# Schematica.net
KiCad netlist of a schematic drawn in EAGLE
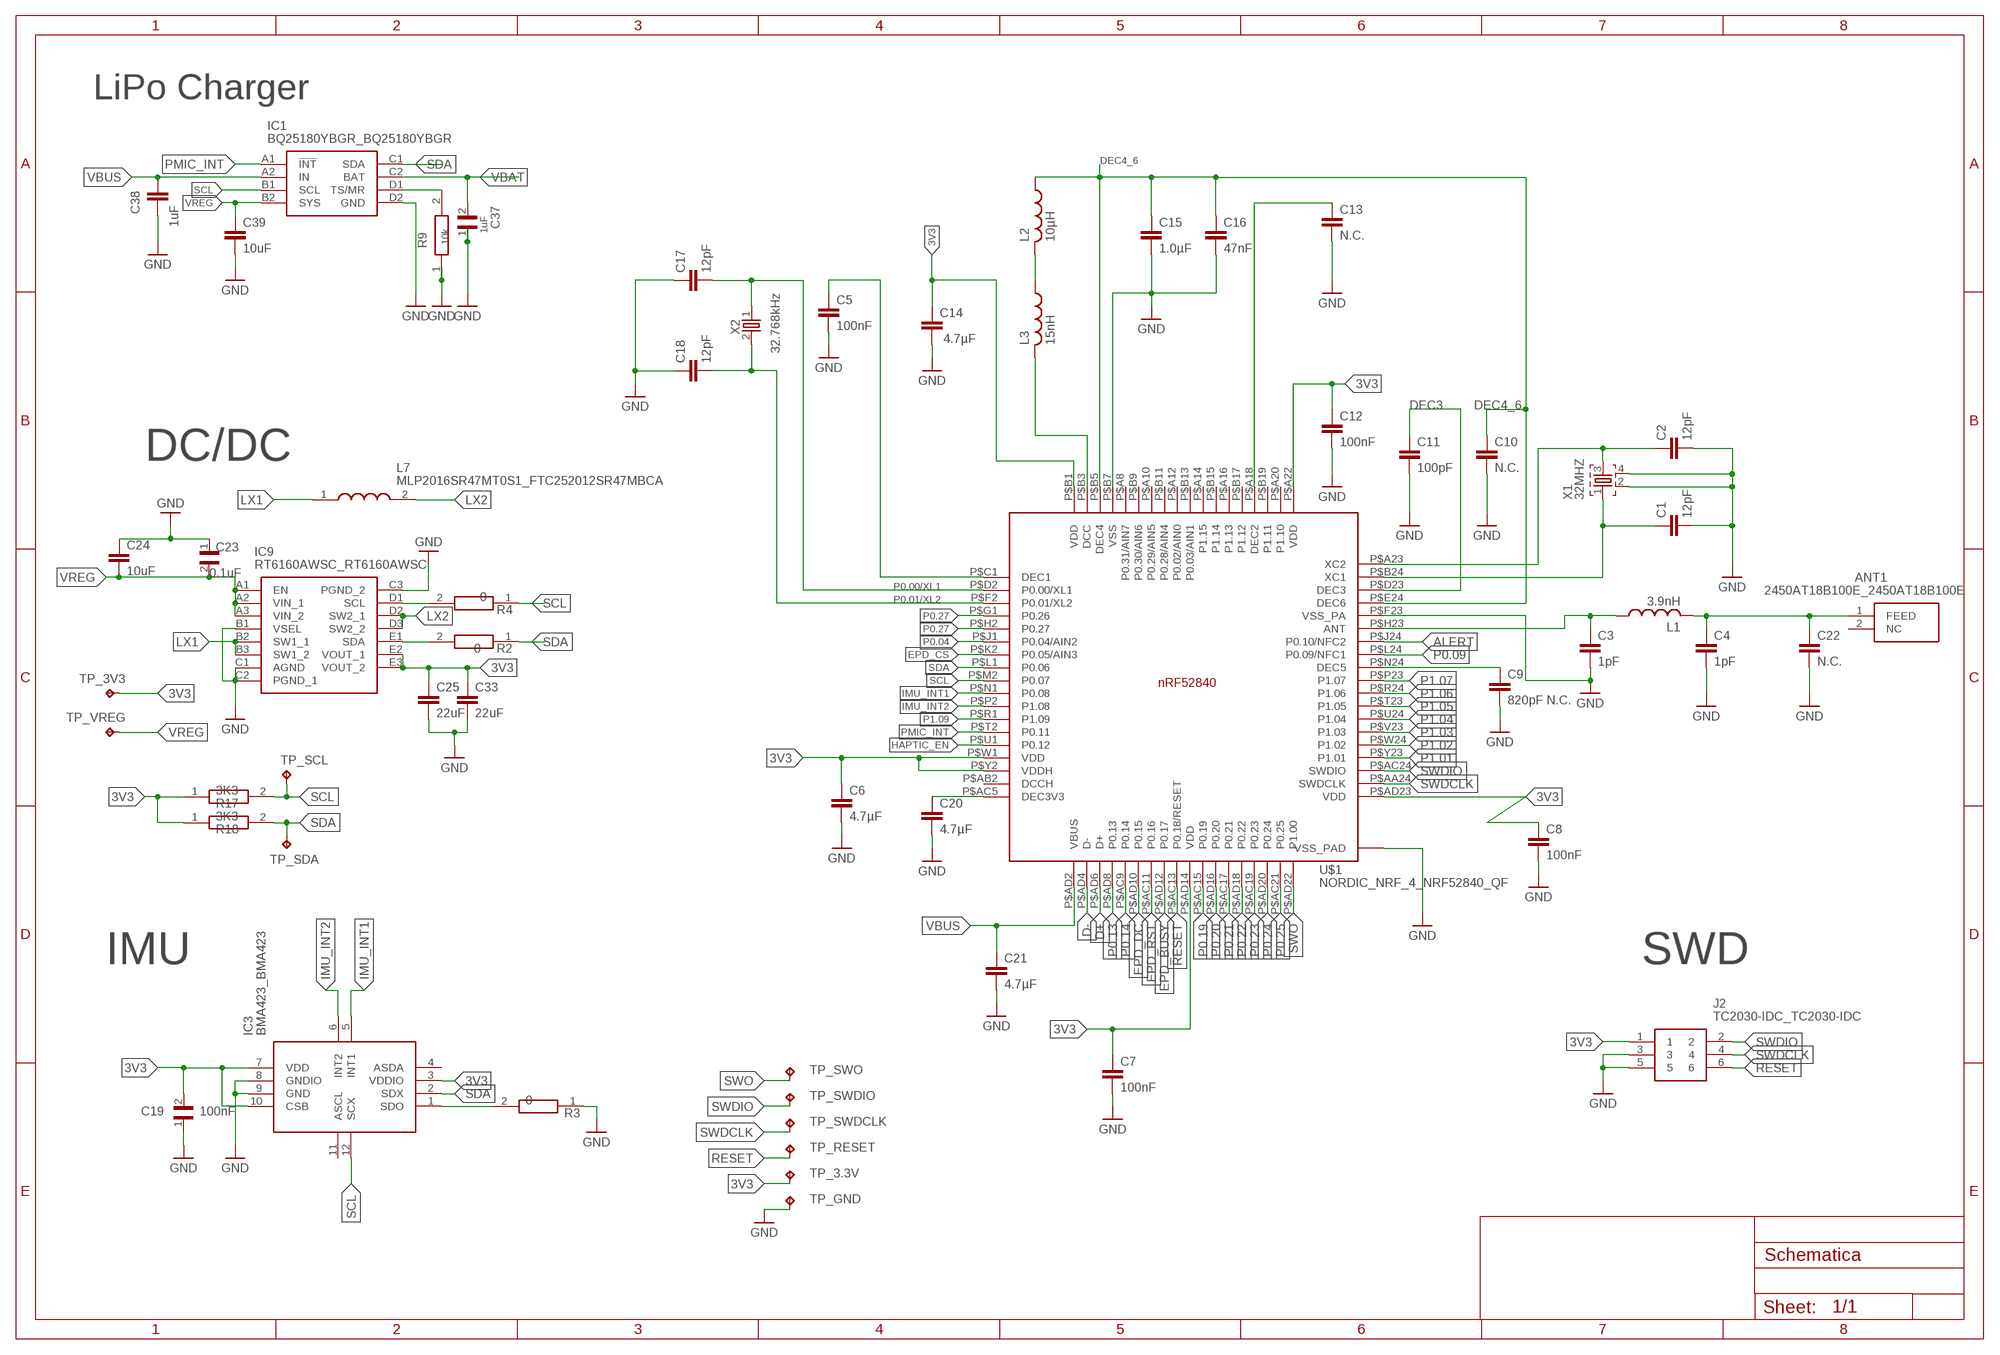
[diagram p0: schematic, sheet 1, part 1 of 2]
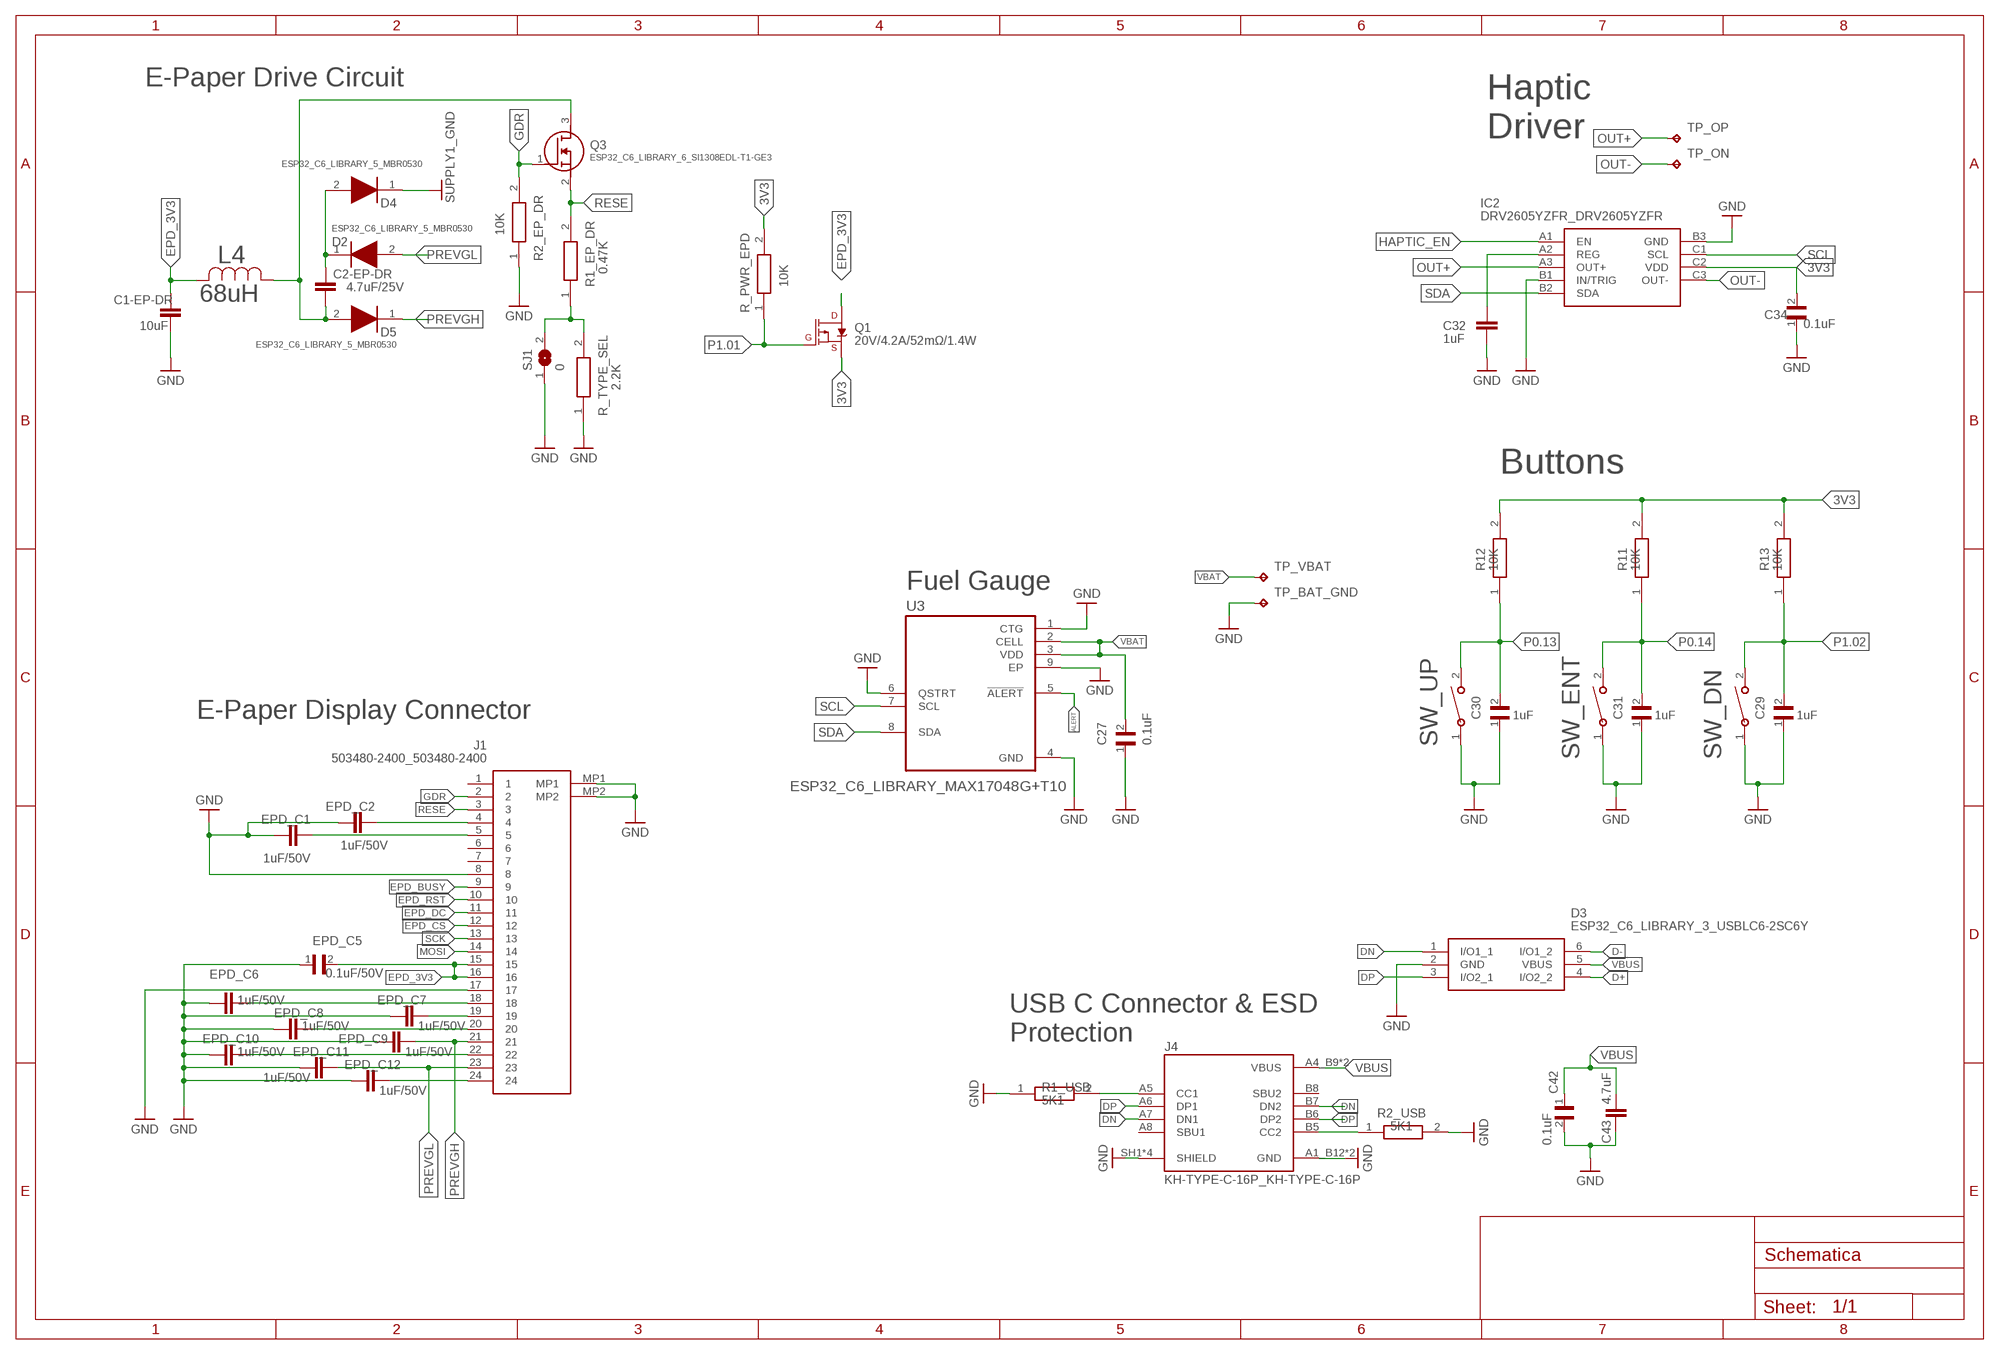
[diagram p1: schematic, sheet 1, part 2 of 2]

(export (version "E")
  (design (tool "Eeschema 10.0.6"))
  (components
    (comp (ref "ANT1")
      (value "2450AT18B100E_2450AT18B100E")
      (footprint "eagle-import:2450AT18B100E_ANTC3216X140N")
      (fields
        (field (name "ARROW_PART_NUMBER") "2450AT18B100E")
        (field (name "MOUSER_PART_NUMBER") "609-2450AT18B100E")
      )
      (libsource (lib "eagle-import") (part "2450AT18B100E_2450AT18B100E"))
    )
    (comp (ref "C1")
      (value "12pF")
      (footprint "eagle-import:NORDIC_NRF_3_RESC0402_L")
      (libsource (lib "eagle-import") (part "NORDIC_NRF_3_CAPACITOR_0402_L"))
    )
    (comp (ref "C1-EP-DR")
      (value "10uF")
      (footprint "eagle-import:PERFECT_0402_0402")
      (libsource (lib "eagle-import") (part "PERFECT_0402_CAP_0402"))
    )
    (comp (ref "C2")
      (value "12pF")
      (footprint "eagle-import:NORDIC_NRF_3_RESC0402_L")
      (libsource (lib "eagle-import") (part "NORDIC_NRF_3_CAPACITOR_0402_L"))
    )
    (comp (ref "C2-EP-DR")
      (value "4.7uF/25V")
      (footprint "eagle-import:PERFECT_0402_0402")
      (libsource (lib "eagle-import") (part "PERFECT_0402_CAP_0402"))
    )
    (comp (ref "C3")
      (value "1pF")
      (footprint "eagle-import:NORDIC_NRF_3_RESC0402_L")
      (libsource (lib "eagle-import") (part "NORDIC_NRF_3_CAPACITOR_0402_L"))
    )
    (comp (ref "C4")
      (value "1pF")
      (footprint "eagle-import:NORDIC_NRF_3_RESC0402_L")
      (libsource (lib "eagle-import") (part "NORDIC_NRF_3_CAPACITOR_0402_L"))
    )
    (comp (ref "C5")
      (value "100nF")
      (footprint "eagle-import:NORDIC_NRF_3_RESC0402_L")
      (libsource (lib "eagle-import") (part "NORDIC_NRF_3_CAPACITOR_0402_L"))
    )
    (comp (ref "C6")
      (value "4.7µF")
      (footprint "eagle-import:NORDIC_NRF_3_RESC0402_L")
      (libsource (lib "eagle-import") (part "NORDIC_NRF_3_CAPACITOR_0402_L"))
    )
    (comp (ref "C7")
      (value "100nF")
      (footprint "eagle-import:NORDIC_NRF_3_RESC0402_L")
      (libsource (lib "eagle-import") (part "NORDIC_NRF_3_CAPACITOR_0402_L"))
    )
    (comp (ref "C8")
      (value "100nF")
      (footprint "eagle-import:NORDIC_NRF_3_RESC0402_L")
      (libsource (lib "eagle-import") (part "NORDIC_NRF_3_CAPACITOR_0402_L"))
    )
    (comp (ref "C9")
      (value "820pF N.C.")
      (footprint "eagle-import:NORDIC_NRF_3_RESC0402_L")
      (libsource (lib "eagle-import") (part "NORDIC_NRF_3_CAPACITOR_0402_L"))
    )
    (comp (ref "C10")
      (value "N.C.")
      (footprint "eagle-import:NORDIC_NRF_3_RESC0402_L")
      (libsource (lib "eagle-import") (part "NORDIC_NRF_3_CAPACITOR_0402_L"))
    )
    (comp (ref "C11")
      (value "100pF")
      (footprint "eagle-import:NORDIC_NRF_3_RESC0402_L")
      (libsource (lib "eagle-import") (part "NORDIC_NRF_3_CAPACITOR_0402_L"))
    )
    (comp (ref "C12")
      (value "100nF")
      (footprint "eagle-import:NORDIC_NRF_3_RESC0402_L")
      (libsource (lib "eagle-import") (part "NORDIC_NRF_3_CAPACITOR_0402_L"))
    )
    (comp (ref "C13")
      (value "N.C.")
      (footprint "eagle-import:NORDIC_NRF_3_RESC0402_L")
      (libsource (lib "eagle-import") (part "NORDIC_NRF_3_CAPACITOR_0402_L"))
    )
    (comp (ref "C14")
      (value "4.7µF")
      (footprint "eagle-import:NORDIC_NRF_3_RESC0402_L")
      (libsource (lib "eagle-import") (part "NORDIC_NRF_3_CAPACITOR_0402_L"))
    )
    (comp (ref "C15")
      (value "1.0µF")
      (footprint "eagle-import:NORDIC_NRF_3_RESC0402_L")
      (libsource (lib "eagle-import") (part "NORDIC_NRF_3_CAPACITOR_0402_L"))
    )
    (comp (ref "C16")
      (value "47nF")
      (footprint "eagle-import:NORDIC_NRF_3_RESC0402_L")
      (libsource (lib "eagle-import") (part "NORDIC_NRF_3_CAPACITOR_0402_L"))
    )
    (comp (ref "C17")
      (value "12pF")
      (footprint "eagle-import:NORDIC_NRF_3_RESC0402_L")
      (libsource (lib "eagle-import") (part "NORDIC_NRF_3_CAPACITOR_0402_L"))
    )
    (comp (ref "C18")
      (value "12pF")
      (footprint "eagle-import:NORDIC_NRF_3_RESC0402_L")
      (libsource (lib "eagle-import") (part "NORDIC_NRF_3_CAPACITOR_0402_L"))
    )
    (comp (ref "C19")
      (value "100nF")
      (footprint "eagle-import:GRM011R60J152KE01L_1_0201")
      (libsource (lib "eagle-import") (part "GRM011R60J152KE01L_1_GRM011R60J152KE01L"))
    )
    (comp (ref "C20")
      (value "4.7µF")
      (footprint "eagle-import:NORDIC_NRF_3_RESC0402_L")
      (libsource (lib "eagle-import") (part "NORDIC_NRF_3_CAPACITOR_0402_L"))
    )
    (comp (ref "C21")
      (value "4.7µF")
      (footprint "eagle-import:NORDIC_NRF_3_RESC0402_L")
      (libsource (lib "eagle-import") (part "NORDIC_NRF_3_CAPACITOR_0402_L"))
    )
    (comp (ref "C22")
      (value "N.C.")
      (footprint "eagle-import:NORDIC_NRF_3_RESC0402_L")
      (libsource (lib "eagle-import") (part "NORDIC_NRF_3_CAPACITOR_0402_L"))
    )
    (comp (ref "C23")
      (value "0.1uF")
      (footprint "eagle-import:GRM011R60J152KE01L_1_0201")
      (libsource (lib "eagle-import") (part "GRM011R60J152KE01L_1_GRM011R60J152KE01L"))
    )
    (comp (ref "C24")
      (value "10uF")
      (footprint "eagle-import:PERFECT_0402_0402")
      (libsource (lib "eagle-import") (part "PERFECT_0402_CAP_0402"))
    )
    (comp (ref "C25")
      (value "22uF")
      (footprint "eagle-import:PERFECT_0402_0402")
      (libsource (lib "eagle-import") (part "PERFECT_0402_CAP_0402"))
    )
    (comp (ref "C27")
      (value "0.1uF")
      (footprint "eagle-import:GRM011R60J152KE01L_1_0201")
      (libsource (lib "eagle-import") (part "GRM011R60J152KE01L_1_GRM011R60J152KE01L"))
    )
    (comp (ref "C29")
      (value "GRM011R60J152KE01L_2_GRM011R60J152KE01L")
      (footprint "eagle-import:GRM011R60J152KE01L_2_CAPC0201X13N")
      (fields (field (name "MF") "Murata") (field (name "MP") "GRM011R60J152KE01L"))
      (libsource (lib "eagle-import") (part "GRM011R60J152KE01L_2_GRM011R60J152KE01L"))
    )
    (comp (ref "C30")
      (value "GRM011R60J152KE01L_2_GRM011R60J152KE01L")
      (footprint "eagle-import:GRM011R60J152KE01L_2_CAPC0201X13N")
      (fields (field (name "MF") "Murata") (field (name "MP") "GRM011R60J152KE01L"))
      (libsource (lib "eagle-import") (part "GRM011R60J152KE01L_2_GRM011R60J152KE01L"))
    )
    (comp (ref "C31")
      (value "GRM011R60J152KE01L_2_GRM011R60J152KE01L")
      (footprint "eagle-import:GRM011R60J152KE01L_2_CAPC0201X13N")
      (fields (field (name "MF") "Murata") (field (name "MP") "GRM011R60J152KE01L"))
      (libsource (lib "eagle-import") (part "GRM011R60J152KE01L_2_GRM011R60J152KE01L"))
    )
    (comp (ref "C32")
      (value "1uF")
      (footprint "eagle-import:PERFECT_0402_0402")
      (libsource (lib "eagle-import") (part "PERFECT_0402_CAP_0402"))
    )
    (comp (ref "C33")
      (value "22uF")
      (footprint "eagle-import:PERFECT_0402_0402")
      (libsource (lib "eagle-import") (part "PERFECT_0402_CAP_0402"))
    )
    (comp (ref "C34")
      (value "0.1uF")
      (footprint "eagle-import:GRM011R60J152KE01L_1_0201")
      (libsource (lib "eagle-import") (part "GRM011R60J152KE01L_1_GRM011R60J152KE01L"))
    )
    (comp (ref "C37")
      (value "GRM011R60J152KE01L_2_GRM011R60J152KE01L")
      (footprint "eagle-import:GRM011R60J152KE01L_2_CAPC0201X13N")
      (fields (field (name "MF") "Murata") (field (name "MP") "GRM011R60J152KE01L"))
      (libsource (lib "eagle-import") (part "GRM011R60J152KE01L_2_GRM011R60J152KE01L"))
    )
    (comp (ref "C38")
      (value "1uF")
      (footprint "eagle-import:PERFECT_0402_0402")
      (libsource (lib "eagle-import") (part "PERFECT_0402_CAP_0402"))
    )
    (comp (ref "C39")
      (value "10uF")
      (footprint "eagle-import:PERFECT_0402_0402")
      (libsource (lib "eagle-import") (part "PERFECT_0402_CAP_0402"))
    )
    (comp (ref "C42")
      (value "0.1uF")
      (footprint "eagle-import:GRM011R60J152KE01L_1_0201")
      (libsource (lib "eagle-import") (part "GRM011R60J152KE01L_1_GRM011R60J152KE01L"))
    )
    (comp (ref "C43")
      (value "4.7uF")
      (footprint "eagle-import:PERFECT_0402_0402")
      (libsource (lib "eagle-import") (part "PERFECT_0402_CAP_0402"))
    )
    (comp (ref "D2")
      (value "ESP32_C6_LIBRARY_5_MBR0530")
      (footprint "eagle-import:ESP32_C6_LIBRARY_5_SOD3716X135N")
      (fields (field (name "MF") "ON Semiconductor") (field (name "MP") "MBR0530"))
      (libsource (lib "eagle-import") (part "ESP32_C6_LIBRARY_5_MBR0530"))
    )
    (comp (ref "D3")
      (value "ESP32_C6_LIBRARY_3_USBLC6-2SC6Y")
      (footprint "eagle-import:ESP32_C6_LIBRARY_3_SOT95P280X145-6N")
      (fields (field (name "MF") "STMicroelectronics") (field (name "MP") "USBLC6-2SC6Y"))
      (libsource (lib "eagle-import") (part "ESP32_C6_LIBRARY_3_USBLC6-2SC6Y"))
    )
    (comp (ref "D4")
      (value "ESP32_C6_LIBRARY_5_MBR0530")
      (footprint "eagle-import:ESP32_C6_LIBRARY_5_SOD3716X135N")
      (fields (field (name "MF") "ON Semiconductor") (field (name "MP") "MBR0530"))
      (libsource (lib "eagle-import") (part "ESP32_C6_LIBRARY_5_MBR0530"))
    )
    (comp (ref "D5")
      (value "ESP32_C6_LIBRARY_5_MBR0530")
      (footprint "eagle-import:ESP32_C6_LIBRARY_5_SOD3716X135N")
      (fields (field (name "MF") "ON Semiconductor") (field (name "MP") "MBR0530"))
      (libsource (lib "eagle-import") (part "ESP32_C6_LIBRARY_5_MBR0530"))
    )
    (comp (ref "EPD_C1")
      (value "1uF/50V")
      (footprint "eagle-import:PERFECT_0402_0402")
      (libsource (lib "eagle-import") (part "PERFECT_0402_CAP_0402"))
    )
    (comp (ref "EPD_C2")
      (value "1uF/50V")
      (footprint "eagle-import:PERFECT_0402_0402")
      (libsource (lib "eagle-import") (part "PERFECT_0402_CAP_0402"))
    )
    (comp (ref "EPD_C5")
      (value "0.1uF/50V")
      (footprint "eagle-import:GRM011R60J152KE01L_1_0201")
      (libsource (lib "eagle-import") (part "GRM011R60J152KE01L_1_GRM011R60J152KE01L"))
    )
    (comp (ref "EPD_C6")
      (value "1uF/50V")
      (footprint "eagle-import:PERFECT_0402_0402")
      (libsource (lib "eagle-import") (part "PERFECT_0402_CAP_0402"))
    )
    (comp (ref "EPD_C7")
      (value "1uF/50V")
      (footprint "eagle-import:PERFECT_0402_0402")
      (libsource (lib "eagle-import") (part "PERFECT_0402_CAP_0402"))
    )
    (comp (ref "EPD_C8")
      (value "1uF/50V")
      (footprint "eagle-import:PERFECT_0402_0402")
      (libsource (lib "eagle-import") (part "PERFECT_0402_CAP_0402"))
    )
    (comp (ref "EPD_C9")
      (value "1uF/50V")
      (footprint "eagle-import:PERFECT_0402_0402")
      (libsource (lib "eagle-import") (part "PERFECT_0402_CAP_0402"))
    )
    (comp (ref "EPD_C10")
      (value "1uF/50V")
      (footprint "eagle-import:PERFECT_0402_0402")
      (libsource (lib "eagle-import") (part "PERFECT_0402_CAP_0402"))
    )
    (comp (ref "EPD_C11")
      (value "1uF/50V")
      (footprint "eagle-import:PERFECT_0402_0402")
      (libsource (lib "eagle-import") (part "PERFECT_0402_CAP_0402"))
    )
    (comp (ref "EPD_C12")
      (value "1uF/50V")
      (footprint "eagle-import:PERFECT_0402_0402")
      (libsource (lib "eagle-import") (part "PERFECT_0402_CAP_0402"))
    )
    (comp (ref "IC1")
      (value "BQ25180YBGR_BQ25180YBGR")
      (footprint "eagle-import:BQ25180YBGR_BGA8C40P2X4_100X155X50")
      (fields
        (field (name "ARROW_PART_NUMBER") "BQ25180YBGR")
        (field (name "MOUSER_PART_NUMBER") "595-BQ25180YBGR")
      )
      (libsource (lib "eagle-import") (part "BQ25180YBGR_BQ25180YBGR"))
    )
    (comp (ref "IC2")
      (value "DRV2605YZFR_DRV2605YZFR")
      (footprint "eagle-import:DRV2605YZFR_BGA9C50P3X3_144X144X62")
      (fields (field (name "ARROW_PART_NUMBER") "DRV2605YZFR"))
      (libsource (lib "eagle-import") (part "DRV2605YZFR_DRV2605YZFR"))
    )
    (comp (ref "IC3")
      (value "BMA423_BMA423")
      (footprint "eagle-import:BMA423_BMA423")
      (fields (field (name "ARROW_PART_NUMBER") "BMA423") (field (name "MOUSER_PART_NUMBER") "262-BMA423"))
      (libsource (lib "eagle-import") (part "BMA423_BMA423"))
    )
    (comp (ref "IC9")
      (value "RT6160AWSC_RT6160AWSC")
      (footprint "eagle-import:RT6160AWSC_BGA15C40P3X5_140X230X60")
      (fields
        (field (name "MANUFACTURER_PART_NUMBER") "RT6160AWSC")
        (field (name "MOUSER_PART_NUMBER") "835-RT6160AWSC")
      )
      (libsource (lib "eagle-import") (part "RT6160AWSC_RT6160AWSC"))
    )
    (comp (ref "J1")
      (value "503480-2400_503480-2400")
      (footprint "eagle-import:503480-2400_5034802400")
      (fields
        (field (name "MANUFACTURER_PART_NUMBER") "503480-2400")
        (field (name "MOUSER_PART_NUMBER") "538-503480-2400")
      )
      (libsource (lib "eagle-import") (part "503480-2400_503480-2400"))
    )
    (comp (ref "J2")
      (value "TC2030-IDC_TC2030-IDC")
      (footprint "eagle-import:TC2030-IDC_TC2030IDC")
      (fields (field (name "MANUFACTURER_PART_NUMBER") "TC2030-IDC"))
      (libsource (lib "eagle-import") (part "TC2030-IDC_TC2030-IDC"))
    )
    (comp (ref "J4")
      (value "KH-TYPE-C-16P_KH-TYPE-C-16P")
      (footprint "eagle-import:KH-TYPE-C-16P_KINGHELM_KH-TYPE-C-16P")
      (fields (field (name "MF") "kinghelm") (field (name "MP") "KH-TYPE-C-16P"))
      (libsource (lib "eagle-import") (part "KH-TYPE-C-16P_KH-TYPE-C-16P"))
    )
    (comp (ref "L1")
      (value "3.9nH")
      (footprint "eagle-import:NORDIC_NRF_2_RESC0402_L")
      (libsource (lib "eagle-import") (part "NORDIC_NRF_2_INDUCTOR_0402_L"))
    )
    (comp (ref "L2")
      (value "10µH")
      (footprint "eagle-import:NORDIC_NRF_2_RESC0402_L")
      (libsource (lib "eagle-import") (part "NORDIC_NRF_2_INDUCTOR_0402_L"))
    )
    (comp (ref "L3")
      (value "15nH")
      (footprint "eagle-import:NORDIC_NRF_2_RESC0402_L")
      (libsource (lib "eagle-import") (part "NORDIC_NRF_2_INDUCTOR_0402_L"))
    )
    (comp (ref "L4")
      (value "68uH")
      (footprint "eagle-import:ESP32_C6_LIBRARY_2_IND_4828-WE-TPC_WRE")
      (fields
        (field (name "MANUFACTURER_PART_NUMBER") "744043680")
        (field (name "COPYRIGHT") "Copyright (C) 2024 Ultra Librarian. All rights reserved.")
      )
      (libsource (lib "eagle-import") (part "ESP32_C6_LIBRARY_2_744043680IND_4828-WE-TPC_WRE"))
    )
    (comp (ref "L7")
      (value "MLP2016SR47MT0S1_FTC252012SR47MBCA")
      (footprint "eagle-import:MLP2016SR47MT0S1_INDC2016X100N")
      (fields (field (name "MANUFACTURER_PART_NUMBER") "FTC252012SR47MBCA"))
      (libsource (lib "eagle-import") (part "MLP2016SR47MT0S1_FTC252012SR47MBCA"))
    )
    (comp (ref "Q1")
      (value "20V/4.2A/52mΩ/1.4W")
      (footprint "eagle-import:ESP32_C6_LIBRARY_4_ESP32_C6_LIBRARY_4_ESP32_C6_LIBRARY_4_ESP32_C6_LIBRARY_4_ESP32_WROVER_SPARKFUN-DISCRETESEMI_SOT23-3")
      (libsource (lib "eagle-import") (part "ESP32_C6_LIBRARY_4_ESP32_WROVER_SPARKFUN-DISCRETESEMI_MOSFET_PCH-DMG2305UX-7"))
    )
    (comp (ref "Q3")
      (value "ESP32_C6_LIBRARY_6_SI1308EDL-T1-GE3")
      (footprint "eagle-import:ESP32_C6_LIBRARY_6_SOT65P210X110-3N")
      (fields (field (name "MF") "Vishay Siliconix") (field (name "MP") "SI1308EDL-T1-GE3"))
      (libsource (lib "eagle-import") (part "ESP32_C6_LIBRARY_6_SI1308EDL-T1-GE3"))
    )
    (comp (ref "R1_EP_DR")
      (value "0.47K")
      (footprint "eagle-import:CPF0201D7K68C1_0201")
      (libsource (lib "eagle-import") (part "CPF0201D7K68C1_CPF0201D7K68C1"))
    )
    (comp (ref "R1_USB")
      (value "5K1")
      (footprint "eagle-import:CPF0201D7K68C1_0201")
      (libsource (lib "eagle-import") (part "CPF0201D7K68C1_CPF0201D7K68C1"))
    )
    (comp (ref "R2")
      (value "0")
      (footprint "eagle-import:CPF0201D7K68C1_0201")
      (libsource (lib "eagle-import") (part "CPF0201D7K68C1_CPF0201D7K68C1"))
    )
    (comp (ref "R2_EP_DR")
      (value "10K")
      (footprint "eagle-import:CPF0201D7K68C1_0201")
      (libsource (lib "eagle-import") (part "CPF0201D7K68C1_CPF0201D7K68C1"))
    )
    (comp (ref "R2_USB")
      (value "5K1")
      (footprint "eagle-import:CPF0201D7K68C1_0201")
      (libsource (lib "eagle-import") (part "CPF0201D7K68C1_CPF0201D7K68C1"))
    )
    (comp (ref "R3")
      (value "0")
      (footprint "eagle-import:CPF0201D7K68C1_0201")
      (libsource (lib "eagle-import") (part "CPF0201D7K68C1_CPF0201D7K68C1"))
    )
    (comp (ref "R4")
      (value "0")
      (footprint "eagle-import:CPF0201D7K68C1_0201")
      (libsource (lib "eagle-import") (part "CPF0201D7K68C1_CPF0201D7K68C1"))
    )
    (comp (ref "R9")
      (value "ERA-1AEB3401C_CPF0201D7K68C1")
      (footprint "eagle-import:ERA-1AEB3401C_0201")
      (libsource (lib "eagle-import") (part "ERA-1AEB3401C_CPF0201D7K68C1"))
    )
    (comp (ref "R11")
      (value "10K")
      (footprint "eagle-import:CPF0201D7K68C1_0201")
      (libsource (lib "eagle-import") (part "CPF0201D7K68C1_CPF0201D7K68C1"))
    )
    (comp (ref "R12")
      (value "10K")
      (footprint "eagle-import:CPF0201D7K68C1_0201")
      (libsource (lib "eagle-import") (part "CPF0201D7K68C1_CPF0201D7K68C1"))
    )
    (comp (ref "R13")
      (value "10K")
      (footprint "eagle-import:CPF0201D7K68C1_0201")
      (libsource (lib "eagle-import") (part "CPF0201D7K68C1_CPF0201D7K68C1"))
    )
    (comp (ref "R17")
      (value "3K3")
      (footprint "eagle-import:CPF0201D7K68C1_0201")
      (libsource (lib "eagle-import") (part "CPF0201D7K68C1_CPF0201D7K68C1"))
    )
    (comp (ref "R18")
      (value "3K3")
      (footprint "eagle-import:CPF0201D7K68C1_0201")
      (libsource (lib "eagle-import") (part "CPF0201D7K68C1_CPF0201D7K68C1"))
    )
    (comp (ref "R_PWR_EPD")
      (value "10K")
      (footprint "eagle-import:CPF0201D7K68C1_0201")
      (libsource (lib "eagle-import") (part "CPF0201D7K68C1_CPF0201D7K68C1"))
    )
    (comp (ref "R_TYPE_SEL")
      (value "2.2K")
      (footprint "eagle-import:CPF0201D7K68C1_0201")
      (libsource (lib "eagle-import") (part "CPF0201D7K68C1_CPF0201D7K68C1"))
    )
    (comp (ref "SJ1")
      (value "0")
      (footprint "eagle-import:ESP32_C6_LIBRARY_7_JUMPER_SJ")
      (libsource (lib "eagle-import") (part "ESP32_C6_LIBRARY_7_JUMPER_SJ"))
    )
    (comp (ref "SW_DN")
      (value "2025-10-22_07-23-44_LIBRARY_EVP-AKE31ASW_EVP-AKE31A_PAN")
      (footprint "eagle-import:2025-10-22_07-23-44_LIBRARY_SW_EVP-AKE31A_PAN")
      (fields
        (field (name "MANUFACTURER_PART_NUMBER") "EVP-AKE31A")
        (field (name "COPYRIGHT") "Copyright (C) 2025 Ultra Librarian. All rights reserved.")
      )
      (libsource (lib "eagle-import") (part "2025-10-22_07-23-44_LIBRARY_EVP-AKE31ASW_EVP-AKE31A_PAN"))
    )
    (comp (ref "SW_ENT")
      (value "2025-10-22_07-23-44_LIBRARY_EVP-AKE31ASW_EVP-AKE31A_PAN")
      (footprint "eagle-import:2025-10-22_07-23-44_LIBRARY_SW_EVP-AKE31A_PAN")
      (fields
        (field (name "MANUFACTURER_PART_NUMBER") "EVP-AKE31A")
        (field (name "COPYRIGHT") "Copyright (C) 2025 Ultra Librarian. All rights reserved.")
      )
      (libsource (lib "eagle-import") (part "2025-10-22_07-23-44_LIBRARY_EVP-AKE31ASW_EVP-AKE31A_PAN"))
    )
    (comp (ref "SW_UP")
      (value "2025-10-22_07-23-44_LIBRARY_EVP-AKE31ASW_EVP-AKE31A_PAN")
      (footprint "eagle-import:2025-10-22_07-23-44_LIBRARY_SW_EVP-AKE31A_PAN")
      (fields
        (field (name "MANUFACTURER_PART_NUMBER") "EVP-AKE31A")
        (field (name "COPYRIGHT") "Copyright (C) 2025 Ultra Librarian. All rights reserved.")
      )
      (libsource (lib "eagle-import") (part "2025-10-22_07-23-44_LIBRARY_EVP-AKE31ASW_EVP-AKE31A_PAN"))
    )
    (comp (ref "TP_3.3V")
      (value "HECTOR_WATCH_1_TPTP20R")
      (footprint "eagle-import:HECTOR_WATCH_1_TP20R")
      (libsource (lib "eagle-import") (part "HECTOR_WATCH_1_TPTP20R"))
    )
    (comp (ref "TP_3V3")
      (value "HECTOR_WATCH_1_TPTP20R")
      (footprint "eagle-import:HECTOR_WATCH_1_TP20R")
      (libsource (lib "eagle-import") (part "HECTOR_WATCH_1_TPTP20R"))
    )
    (comp (ref "TP_BAT_GND")
      (value "HECTOR_WATCH_1_TPTP20R")
      (footprint "eagle-import:HECTOR_WATCH_1_TP20R")
      (libsource (lib "eagle-import") (part "HECTOR_WATCH_1_TPTP20R"))
    )
    (comp (ref "TP_GND")
      (value "HECTOR_WATCH_1_TPTP20R")
      (footprint "eagle-import:HECTOR_WATCH_1_TP20R")
      (libsource (lib "eagle-import") (part "HECTOR_WATCH_1_TPTP20R"))
    )
    (comp (ref "TP_ON")
      (value "HECTOR_WATCH_1_TPTP20R")
      (footprint "eagle-import:HECTOR_WATCH_1_TP20R")
      (libsource (lib "eagle-import") (part "HECTOR_WATCH_1_TPTP20R"))
    )
    (comp (ref "TP_OP")
      (value "HECTOR_WATCH_1_TPTP20R")
      (footprint "eagle-import:HECTOR_WATCH_1_TP20R")
      (libsource (lib "eagle-import") (part "HECTOR_WATCH_1_TPTP20R"))
    )
    (comp (ref "TP_RESET")
      (value "HECTOR_WATCH_1_TPTP20R")
      (footprint "eagle-import:HECTOR_WATCH_1_TP20R")
      (libsource (lib "eagle-import") (part "HECTOR_WATCH_1_TPTP20R"))
    )
    (comp (ref "TP_SCL")
      (value "HECTOR_WATCH_1_TPTP20R")
      (footprint "eagle-import:HECTOR_WATCH_1_TP20R")
      (libsource (lib "eagle-import") (part "HECTOR_WATCH_1_TPTP20R"))
    )
    (comp (ref "TP_SDA")
      (value "HECTOR_WATCH_1_TPTP20R")
      (footprint "eagle-import:HECTOR_WATCH_1_TP20R")
      (libsource (lib "eagle-import") (part "HECTOR_WATCH_1_TPTP20R"))
    )
    (comp (ref "TP_SWDCLK")
      (value "HECTOR_WATCH_1_TPTP20R")
      (footprint "eagle-import:HECTOR_WATCH_1_TP20R")
      (libsource (lib "eagle-import") (part "HECTOR_WATCH_1_TPTP20R"))
    )
    (comp (ref "TP_SWDIO")
      (value "HECTOR_WATCH_1_TPTP20R")
      (footprint "eagle-import:HECTOR_WATCH_1_TP20R")
      (libsource (lib "eagle-import") (part "HECTOR_WATCH_1_TPTP20R"))
    )
    (comp (ref "TP_SWO")
      (value "HECTOR_WATCH_1_TPTP20R")
      (footprint "eagle-import:HECTOR_WATCH_1_TP20R")
      (libsource (lib "eagle-import") (part "HECTOR_WATCH_1_TPTP20R"))
    )
    (comp (ref "TP_VBAT")
      (value "HECTOR_WATCH_1_TPTP20R")
      (footprint "eagle-import:HECTOR_WATCH_1_TP20R")
      (libsource (lib "eagle-import") (part "HECTOR_WATCH_1_TPTP20R"))
    )
    (comp (ref "TP_VREG")
      (value "HECTOR_WATCH_1_TPTP20R")
      (footprint "eagle-import:HECTOR_WATCH_1_TP20R")
      (libsource (lib "eagle-import") (part "HECTOR_WATCH_1_TPTP20R"))
    )
    (comp (ref "U$1")
      (value "NORDIC_NRF_4_NRF52840_QF")
      (footprint "eagle-import:NORDIC_NRF_4_AQFN50P700X700X85_HS-74N")
      (libsource (lib "eagle-import") (part "NORDIC_NRF_4_NRF52840_QF"))
    )
    (comp (ref "U3")
      (value "ESP32_C6_LIBRARY_MAX17048G+T10")
      (footprint "eagle-import:ESP32_C6_LIBRARY_SON50P200X200X80-9N")
      (fields (field (name "MF") "Analog Devices") (field (name "MP") "MAX17048G+T10"))
      (libsource (lib "eagle-import") (part "ESP32_C6_LIBRARY_MAX17048G+T10"))
    )
    (comp (ref "X1")
      (value "32MHZ")
      (footprint "eagle-import:NORDIC_NRF_BT-XTAL_2016_N")
      (libsource (lib "eagle-import") (part "NORDIC_NRF_XTAL_32MHZ"))
    )
    (comp (ref "X2")
      (value "32.768kHz")
      (footprint "eagle-import:NORDIC_NRF_1_XTAL_3215_N")
      (libsource (lib "eagle-import") (part "NORDIC_NRF_1_XTAL_32KHZ"))
    )
  )
  (nets
    (net (code "1") (name "/DEC3") (class "Default")
      (node (ref "C11") (pin "1") (pinfunction "1_1") (pintype "passive"))
      (node (ref "U$1") (pin "P$D23") (pinfunction "DEC3_P$D23") (pintype "bidirectional"))
    )
    (net (code "2") (name "/DEC4_6") (class "Default")
      (node (ref "C10") (pin "1") (pinfunction "1_1") (pintype "passive"))
      (node (ref "C15") (pin "1") (pinfunction "1_1") (pintype "passive"))
      (node (ref "C16") (pin "1") (pinfunction "1_1") (pintype "passive"))
      (node (ref "L2") (pin "1") (pinfunction "1_1") (pintype "passive"))
      (node (ref "U$1") (pin "P$B5") (pinfunction "DEC4_P$B5") (pintype "power_in"))
      (node (ref "U$1") (pin "P$E24") (pinfunction "DEC6_P$E24") (pintype "bidirectional"))
    )
    (net (code "3") (name "/P0.00{slash}XL1") (class "Default")
      (node (ref "C17") (pin "2") (pinfunction "2_2") (pintype "passive"))
      (node (ref "U$1") (pin "P$D2") (pinfunction "P0.00/XL1_P$D2") (pintype "bidirectional"))
      (node (ref "X2") (pin "1") (pinfunction "1_1") (pintype "passive"))
    )
    (net (code "4") (name "/P0.01{slash}XL2") (class "Default")
      (node (ref "C18") (pin "2") (pinfunction "2_2") (pintype "passive"))
      (node (ref "U$1") (pin "P$F2") (pinfunction "P0.01/XL2_P$F2") (pintype "bidirectional"))
      (node (ref "X2") (pin "2") (pinfunction "2_2") (pintype "passive"))
    )
    (net (code "5") (name "3V3") (class "Default")
      (node (ref "C12") (pin "1") (pinfunction "1_1") (pintype "passive"))
      (node (ref "C14") (pin "1") (pinfunction "1_1") (pintype "passive"))
      (node (ref "C19") (pin "2") (pinfunction "2_2") (pintype "passive"))
      (node (ref "C25") (pin "1") (pinfunction "1_1") (pintype "passive"))
      (node (ref "C33") (pin "1") (pinfunction "1_1") (pintype "passive"))
      (node (ref "C34") (pin "2") (pinfunction "2_2") (pintype "passive"))
      (node (ref "C6") (pin "1") (pinfunction "1_1") (pintype "passive"))
      (node (ref "C7") (pin "1") (pinfunction "1_1") (pintype "passive"))
      (node (ref "C8") (pin "1") (pinfunction "1_1") (pintype "passive"))
      (node (ref "IC2") (pin "C2") (pinfunction "VDD_C2") (pintype "bidirectional"))
      (node (ref "IC3") (pin "10") (pinfunction "CSB_10") (pintype "bidirectional"))
      (node (ref "IC3") (pin "3") (pinfunction "VDDIO_3") (pintype "bidirectional"))
      (node (ref "IC3") (pin "7") (pinfunction "VDD_7") (pintype "bidirectional"))
      (node (ref "IC9") (pin "E2") (pinfunction "VOUT_1_E2") (pintype "bidirectional"))
      (node (ref "IC9") (pin "E3") (pinfunction "VOUT_2_E3") (pintype "bidirectional"))
      (node (ref "J2") (pin "1") (pinfunction "1_1") (pintype "bidirectional"))
      (node (ref "Q1") (pin "2") (pinfunction "S_2") (pintype "bidirectional"))
      (node (ref "R11") (pin "2") (pinfunction "2_2") (pintype "bidirectional"))
      (node (ref "R12") (pin "2") (pinfunction "2_2") (pintype "bidirectional"))
      (node (ref "R13") (pin "2") (pinfunction "2_2") (pintype "bidirectional"))
      (node (ref "R17") (pin "1") (pinfunction "1_1") (pintype "bidirectional"))
      (node (ref "R18") (pin "1") (pinfunction "1_1") (pintype "bidirectional"))
      (node (ref "R_PWR_EPD") (pin "2") (pinfunction "2_2") (pintype "bidirectional"))
      (node (ref "TP_3.3V") (pin "TP") (pinfunction "TP_TP") (pintype "input"))
      (node (ref "TP_3V3") (pin "TP") (pinfunction "TP_TP") (pintype "input"))
      (node (ref "U$1") (pin "P$A22") (pinfunction "VDD_P$A22") (pintype "power_in"))
      (node (ref "U$1") (pin "P$AD14") (pinfunction "VDD_P$AD14") (pintype "power_in"))
      (node (ref "U$1") (pin "P$AD23") (pinfunction "VDD_P$AD23") (pintype "power_in"))
      (node (ref "U$1") (pin "P$B1") (pinfunction "VDD_P$B1") (pintype "power_in"))
      (node (ref "U$1") (pin "P$W1") (pinfunction "VDD_P$W1") (pintype "power_in"))
      (node (ref "U$1") (pin "P$Y2") (pinfunction "VDDH_P$Y2") (pintype "power_in"))
    )
    (net (code "6") (name "ALERT") (class "Default")
      (node (ref "U$1") (pin "P$J24") (pinfunction "P0.10/NFC2_P$J24") (pintype "bidirectional"))
      (node (ref "U3") (pin "5") (pinfunction "~{ALERT}_5") (pintype "output"))
    )
    (net (code "7") (name "D+") (class "Default")
      (node (ref "D3") (pin "4") (pinfunction "I/O2_2_4") (pintype "bidirectional"))
      (node (ref "U$1") (pin "P$AD6") (pinfunction "D+_P$AD6") (pintype "bidirectional"))
    )
    (net (code "8") (name "D-") (class "Default")
      (node (ref "D3") (pin "6") (pinfunction "I/O1_2_6") (pintype "bidirectional"))
      (node (ref "U$1") (pin "P$AD4") (pinfunction "D-_P$AD4") (pintype "bidirectional"))
    )
    (net (code "9") (name "DN") (class "Default")
      (node (ref "D3") (pin "1") (pinfunction "I/O1_1_1") (pintype "bidirectional"))
      (node (ref "J4") (pin "A7") (pinfunction "DN1_A7") (pintype "bidirectional"))
      (node (ref "J4") (pin "B7") (pinfunction "DN2_B7") (pintype "bidirectional"))
    )
    (net (code "10") (name "DP") (class "Default")
      (node (ref "D3") (pin "3") (pinfunction "I/O2_1_3") (pintype "bidirectional"))
      (node (ref "J4") (pin "A6") (pinfunction "DP1_A6") (pintype "bidirectional"))
      (node (ref "J4") (pin "B6") (pinfunction "DP2_B6") (pintype "bidirectional"))
    )
    (net (code "11") (name "EPD_3V3") (class "Default")
      (node (ref "C1-EP-DR") (pin "1") (pinfunction "1_1") (pintype "passive"))
      (node (ref "EPD_C5") (pin "2") (pinfunction "2_2") (pintype "passive"))
      (node (ref "J1") (pin "15") (pinfunction "15_15") (pintype "bidirectional"))
      (node (ref "J1") (pin "16") (pinfunction "16_16") (pintype "bidirectional"))
      (node (ref "L4") (pin "2") (pinfunction "2_2") (pintype "passive"))
      (node (ref "Q1") (pin "3") (pinfunction "D_3") (pintype "bidirectional"))
    )
    (net (code "12") (name "EPD_BUSY") (class "Default")
      (node (ref "J1") (pin "9") (pinfunction "9_9") (pintype "bidirectional"))
      (node (ref "U$1") (pin "P$AD12") (pinfunction "P0.17_P$AD12") (pintype "bidirectional"))
    )
    (net (code "13") (name "EPD_CS") (class "Default")
      (node (ref "J1") (pin "12") (pinfunction "12_12") (pintype "bidirectional"))
      (node (ref "U$1") (pin "P$K2") (pinfunction "P0.05/AIN3_P$K2") (pintype "bidirectional"))
    )
    (net (code "14") (name "EPD_DC") (class "Default")
      (node (ref "J1") (pin "11") (pinfunction "11_11") (pintype "bidirectional"))
      (node (ref "U$1") (pin "P$AD10") (pinfunction "P0.15_P$AD10") (pintype "bidirectional"))
    )
    (net (code "15") (name "EPD_RST") (class "Default")
      (node (ref "J1") (pin "10") (pinfunction "10_10") (pintype "bidirectional"))
      (node (ref "U$1") (pin "P$AC11") (pinfunction "P0.16_P$AC11") (pintype "bidirectional"))
    )
    (net (code "16") (name "GDR") (class "Default")
      (node (ref "J1") (pin "2") (pinfunction "2_2") (pintype "bidirectional"))
      (node (ref "Q3") (pin "1") (pinfunction "G_1") (pintype "bidirectional"))
      (node (ref "R2_EP_DR") (pin "2") (pinfunction "2_2") (pintype "bidirectional"))
    )
    (net (code "17") (name "GND") (class "Default")
      (node (ref "C1") (pin "2") (pinfunction "2_2") (pintype "passive"))
      (node (ref "C1-EP-DR") (pin "2") (pinfunction "2_2") (pintype "passive"))
      (node (ref "C10") (pin "2") (pinfunction "2_2") (pintype "passive"))
      (node (ref "C11") (pin "2") (pinfunction "2_2") (pintype "passive"))
      (node (ref "C12") (pin "2") (pinfunction "2_2") (pintype "passive"))
      (node (ref "C13") (pin "2") (pinfunction "2_2") (pintype "passive"))
      (node (ref "C14") (pin "2") (pinfunction "2_2") (pintype "passive"))
      (node (ref "C15") (pin "2") (pinfunction "2_2") (pintype "passive"))
      (node (ref "C16") (pin "2") (pinfunction "2_2") (pintype "passive"))
      (node (ref "C17") (pin "1") (pinfunction "1_1") (pintype "passive"))
      (node (ref "C18") (pin "1") (pinfunction "1_1") (pintype "passive"))
      (node (ref "C19") (pin "1") (pinfunction "1_1") (pintype "passive"))
      (node (ref "C2") (pin "2") (pinfunction "2_2") (pintype "passive"))
      (node (ref "C20") (pin "2") (pinfunction "2_2") (pintype "passive"))
      (node (ref "C21") (pin "2") (pinfunction "2_2") (pintype "passive"))
      (node (ref "C22") (pin "2") (pinfunction "2_2") (pintype "passive"))
      (node (ref "C23") (pin "1") (pinfunction "1_1") (pintype "passive"))
      (node (ref "C24") (pin "1") (pinfunction "1_1") (pintype "passive"))
      (node (ref "C25") (pin "2") (pinfunction "2_2") (pintype "passive"))
      (node (ref "C27") (pin "1") (pinfunction "1_1") (pintype "passive"))
      (node (ref "C29") (pin "1") (pinfunction "1_1") (pintype "passive"))
      (node (ref "C3") (pin "2") (pinfunction "2_2") (pintype "passive"))
      (node (ref "C30") (pin "1") (pinfunction "1_1") (pintype "passive"))
      (node (ref "C31") (pin "1") (pinfunction "1_1") (pintype "passive"))
      (node (ref "C32") (pin "2") (pinfunction "2_2") (pintype "passive"))
      (node (ref "C33") (pin "2") (pinfunction "2_2") (pintype "passive"))
      (node (ref "C34") (pin "1") (pinfunction "1_1") (pintype "passive"))
      (node (ref "C37") (pin "1") (pinfunction "1_1") (pintype "passive"))
      (node (ref "C38") (pin "2") (pinfunction "2_2") (pintype "passive"))
      (node (ref "C39") (pin "2") (pinfunction "2_2") (pintype "passive"))
      (node (ref "C4") (pin "2") (pinfunction "2_2") (pintype "passive"))
      (node (ref "C42") (pin "2") (pinfunction "2_2") (pintype "passive"))
      (node (ref "C43") (pin "2") (pinfunction "2_2") (pintype "passive"))
      (node (ref "C5") (pin "2") (pinfunction "2_2") (pintype "passive"))
      (node (ref "C6") (pin "2") (pinfunction "2_2") (pintype "passive"))
      (node (ref "C7") (pin "2") (pinfunction "2_2") (pintype "passive"))
      (node (ref "C8") (pin "2") (pinfunction "2_2") (pintype "passive"))
      (node (ref "C9") (pin "2") (pinfunction "2_2") (pintype "passive"))
      (node (ref "D3") (pin "2") (pinfunction "GND_2") (pintype "bidirectional"))
      (node (ref "D4") (pin "1") (pinfunction "K_1") (pintype "bidirectional"))
      (node (ref "EPD_C1") (pin "1") (pinfunction "1_1") (pintype "passive"))
      (node (ref "EPD_C10") (pin "1") (pinfunction "1_1") (pintype "passive"))
      (node (ref "EPD_C11") (pin "1") (pinfunction "1_1") (pintype "passive"))
      (node (ref "EPD_C12") (pin "1") (pinfunction "1_1") (pintype "passive"))
      (node (ref "EPD_C2") (pin "1") (pinfunction "1_1") (pintype "passive"))
      (node (ref "EPD_C5") (pin "1") (pinfunction "1_1") (pintype "passive"))
      (node (ref "EPD_C6") (pin "1") (pinfunction "1_1") (pintype "passive"))
      (node (ref "EPD_C7") (pin "1") (pinfunction "1_1") (pintype "passive"))
      (node (ref "EPD_C8") (pin "1") (pinfunction "1_1") (pintype "passive"))
      (node (ref "EPD_C9") (pin "1") (pinfunction "1_1") (pintype "passive"))
      (node (ref "IC1") (pin "D2") (pinfunction "GND_D2") (pintype "bidirectional"))
      (node (ref "IC2") (pin "B1") (pinfunction "IN/TRIG_B1") (pintype "bidirectional"))
      (node (ref "IC2") (pin "B3") (pinfunction "GND_B3") (pintype "bidirectional"))
      (node (ref "IC3") (pin "8") (pinfunction "GNDIO_8") (pintype "bidirectional"))
      (node (ref "IC3") (pin "9") (pinfunction "GND_9") (pintype "bidirectional"))
      (node (ref "IC9") (pin "B1") (pinfunction "VSEL_B1") (pintype "bidirectional"))
      (node (ref "IC9") (pin "C1") (pinfunction "AGND_C1") (pintype "bidirectional"))
      (node (ref "IC9") (pin "C2") (pinfunction "PGND_1_C2") (pintype "bidirectional"))
      (node (ref "IC9") (pin "C3") (pinfunction "PGND_2_C3") (pintype "bidirectional"))
      (node (ref "J1") (pin "17") (pinfunction "17_17") (pintype "bidirectional"))
      (node (ref "J1") (pin "8") (pinfunction "8_8") (pintype "bidirectional"))
      (node (ref "J1") (pin "MP1") (pinfunction "MP1_MP1") (pintype "bidirectional"))
      (node (ref "J1") (pin "MP2") (pinfunction "MP2_MP2") (pintype "bidirectional"))
      (node (ref "J2") (pin "3") (pinfunction "3_3") (pintype "bidirectional"))
      (node (ref "J2") (pin "5") (pinfunction "5_5") (pintype "bidirectional"))
      (node (ref "J4") (pin "A12_B1") (pinfunction "GND_A12_B1") (pintype "power_in"))
      (node (ref "J4") (pin "A1_B12") (pinfunction "GND_A1_B12") (pintype "power_in"))
      (node (ref "J4") (pin "SH1") (pinfunction "SHIELD_SH1") (pintype "passive"))
      (node (ref "J4") (pin "SH2") (pinfunction "SHIELD_SH2") (pintype "passive"))
      (node (ref "J4") (pin "SH3") (pinfunction "SHIELD_SH3") (pintype "passive"))
      (node (ref "J4") (pin "SH4") (pinfunction "SHIELD_SH4") (pintype "passive"))
      (node (ref "R1_USB") (pin "1") (pinfunction "1_1") (pintype "bidirectional"))
      (node (ref "R2_EP_DR") (pin "1") (pinfunction "1_1") (pintype "bidirectional"))
      (node (ref "R2_USB") (pin "2") (pinfunction "2_2") (pintype "bidirectional"))
      (node (ref "R3") (pin "1") (pinfunction "1_1") (pintype "bidirectional"))
      (node (ref "R9") (pin "1") (pinfunction "1_1") (pintype "bidirectional"))
      (node (ref "R_TYPE_SEL") (pin "1") (pinfunction "1_1") (pintype "bidirectional"))
      (node (ref "SJ1") (pin "1") (pinfunction "1_1") (pintype "passive"))
      (node (ref "SW_DN") (pin "1") (pinfunction "1_1") (pintype "passive"))
      (node (ref "SW_ENT") (pin "1") (pinfunction "1_1") (pintype "passive"))
      (node (ref "SW_UP") (pin "1") (pinfunction "1_1") (pintype "passive"))
      (node (ref "TP_BAT_GND") (pin "TP") (pinfunction "TP_TP") (pintype "input"))
      (node (ref "TP_GND") (pin "TP") (pinfunction "TP_TP") (pintype "input"))
      (node (ref "U$1") (pin "P$74") (pinfunction "VSS_PAD_P$74") (pintype "bidirectional"))
      (node (ref "U$1") (pin "P$75") (pinfunction "VSS_PAD_P$75") (pintype "bidirectional"))
      (node (ref "U$1") (pin "P$76") (pinfunction "VSS_PAD_P$76") (pintype "bidirectional"))
      (node (ref "U$1") (pin "P$77") (pinfunction "VSS_PAD_P$77") (pintype "bidirectional"))
      (node (ref "U$1") (pin "P$78") (pinfunction "VSS_PAD_P$78") (pintype "bidirectional"))
      (node (ref "U$1") (pin "P$79") (pinfunction "VSS_PAD_P$79") (pintype "bidirectional"))
      (node (ref "U$1") (pin "P$80") (pinfunction "VSS_PAD_P$80") (pintype "bidirectional"))
      (node (ref "U$1") (pin "P$81") (pinfunction "VSS_PAD_P$81") (pintype "bidirectional"))
      (node (ref "U$1") (pin "P$82") (pinfunction "VSS_PAD_P$82") (pintype "bidirectional"))
      (node (ref "U$1") (pin "P$83") (pinfunction "VSS_PAD_P$83") (pintype "bidirectional"))
      (node (ref "U$1") (pin "P$84") (pinfunction "VSS_PAD_P$84") (pintype "bidirectional"))
      (node (ref "U$1") (pin "P$85") (pinfunction "VSS_PAD_P$85") (pintype "bidirectional"))
      (node (ref "U$1") (pin "P$86") (pinfunction "VSS_PAD_P$86") (pintype "bidirectional"))
      (node (ref "U$1") (pin "P$87") (pinfunction "VSS_PAD_P$87") (pintype "bidirectional"))
      (node (ref "U$1") (pin "P$88") (pinfunction "VSS_PAD_P$88") (pintype "bidirectional"))
      (node (ref "U$1") (pin "P$89") (pinfunction "VSS_PAD_P$89") (pintype "bidirectional"))
      (node (ref "U$1") (pin "P$90") (pinfunction "VSS_PAD_P$90") (pintype "bidirectional"))
      (node (ref "U$1") (pin "P$B7") (pinfunction "VSS_P$B7") (pintype "power_in"))
      (node (ref "U$1") (pin "P$F23") (pinfunction "VSS_PA_P$F23") (pintype "bidirectional"))
      (node (ref "U3") (pin "1") (pinfunction "CTG_1") (pintype "power_in"))
      (node (ref "U3") (pin "4") (pinfunction "GND_4") (pintype "power_in"))
      (node (ref "U3") (pin "6") (pinfunction "QSTRT_6") (pintype "input"))
      (node (ref "U3") (pin "9") (pinfunction "EP_9") (pintype "power_in"))
      (node (ref "X1") (pin "2") (pinfunction "2_2") (pintype "passive"))
      (node (ref "X1") (pin "4") (pinfunction "4_4") (pintype "passive"))
    )
    (net (code "18") (name "HAPTIC_EN") (class "Default")
      (node (ref "IC2") (pin "A1") (pinfunction "EN_A1") (pintype "bidirectional"))
      (node (ref "U$1") (pin "P$U1") (pinfunction "P0.12_P$U1") (pintype "bidirectional"))
    )
    (net (code "19") (name "IMU_INT1") (class "Default")
      (node (ref "IC3") (pin "5") (pinfunction "INT1_5") (pintype "bidirectional"))
      (node (ref "U$1") (pin "P$N1") (pinfunction "P0.08_P$N1") (pintype "bidirectional"))
    )
    (net (code "20") (name "IMU_INT2") (class "Default")
      (node (ref "IC3") (pin "6") (pinfunction "INT2_6") (pintype "bidirectional"))
      (node (ref "U$1") (pin "P$P2") (pinfunction "P1.08_P$P2") (pintype "bidirectional"))
    )
    (net (code "21") (name "LX1") (class "Default")
      (node (ref "IC9") (pin "B2") (pinfunction "SW1_1_B2") (pintype "bidirectional"))
      (node (ref "IC9") (pin "B3") (pinfunction "SW1_2_B3") (pintype "bidirectional"))
      (node (ref "L7") (pin "1") (pinfunction "1_1") (pintype "bidirectional"))
    )
    (net (code "22") (name "LX2") (class "Default")
      (node (ref "IC9") (pin "D2") (pinfunction "SW2_1_D2") (pintype "bidirectional"))
      (node (ref "IC9") (pin "D3") (pinfunction "SW2_2_D3") (pintype "bidirectional"))
      (node (ref "L7") (pin "2") (pinfunction "2_2") (pintype "bidirectional"))
    )
    (net (code "23") (name "MOSI") (class "Default")
      (node (ref "J1") (pin "14") (pinfunction "14_14") (pintype "bidirectional"))
    )
    (net (code "24") (name "Net-(ANT1-FEED)") (class "Default")
      (node (ref "ANT1") (pin "1") (pinfunction "FEED_1") (pintype "input"))
      (node (ref "C22") (pin "1") (pinfunction "1_1") (pintype "passive"))
      (node (ref "C4") (pin "1") (pinfunction "1_1") (pintype "passive"))
      (node (ref "L1") (pin "2") (pinfunction "2_2") (pintype "passive"))
    )
    (net (code "25") (name "Net-(D2-K)") (class "Default")
      (node (ref "C2-EP-DR") (pin "1") (pinfunction "1_1") (pintype "passive"))
      (node (ref "D2") (pin "1") (pinfunction "K_1") (pintype "bidirectional"))
      (node (ref "D4") (pin "2") (pinfunction "A_2") (pintype "bidirectional"))
    )
    (net (code "26") (name "Net-(D5-A)") (class "Default")
      (node (ref "C2-EP-DR") (pin "2") (pinfunction "2_2") (pintype "passive"))
      (node (ref "D5") (pin "2") (pinfunction "A_2") (pintype "bidirectional"))
      (node (ref "L4") (pin "1") (pinfunction "1_1") (pintype "passive"))
      (node (ref "Q3") (pin "3") (pinfunction "D_3") (pintype "bidirectional"))
    )
    (net (code "27") (name "Net-(EPD_C1-Pad2)") (class "Default")
      (node (ref "EPD_C1") (pin "2") (pinfunction "2_2") (pintype "passive"))
      (node (ref "J1") (pin "5") (pinfunction "5_5") (pintype "bidirectional"))
    )
    (net (code "28") (name "Net-(EPD_C2-Pad2)") (class "Default")
      (node (ref "EPD_C2") (pin "2") (pinfunction "2_2") (pintype "passive"))
      (node (ref "J1") (pin "4") (pinfunction "4_4") (pintype "bidirectional"))
    )
    (net (code "29") (name "Net-(EPD_C6-Pad2)") (class "Default")
      (node (ref "EPD_C6") (pin "2") (pinfunction "2_2") (pintype "passive"))
      (node (ref "J1") (pin "18") (pinfunction "18_18") (pintype "bidirectional"))
    )
    (net (code "30") (name "Net-(EPD_C7-Pad2)") (class "Default")
      (node (ref "EPD_C7") (pin "2") (pinfunction "2_2") (pintype "passive"))
      (node (ref "J1") (pin "19") (pinfunction "19_19") (pintype "bidirectional"))
    )
    (net (code "31") (name "Net-(EPD_C8-Pad2)") (class "Default")
      (node (ref "EPD_C8") (pin "2") (pinfunction "2_2") (pintype "passive"))
      (node (ref "J1") (pin "20") (pinfunction "20_20") (pintype "bidirectional"))
    )
    (net (code "32") (name "Net-(EPD_C10-Pad2)") (class "Default")
      (node (ref "EPD_C10") (pin "2") (pinfunction "2_2") (pintype "passive"))
      (node (ref "J1") (pin "22") (pinfunction "22_22") (pintype "bidirectional"))
    )
    (net (code "33") (name "Net-(EPD_C12-Pad2)") (class "Default")
      (node (ref "EPD_C12") (pin "2") (pinfunction "2_2") (pintype "passive"))
      (node (ref "J1") (pin "24") (pinfunction "24_24") (pintype "bidirectional"))
    )
    (net (code "34") (name "Net-(IC1-TS{slash}MR)") (class "Default")
      (node (ref "IC1") (pin "D1") (pinfunction "TS/MR_D1") (pintype "bidirectional"))
      (node (ref "R9") (pin "2") (pinfunction "2_2") (pintype "bidirectional"))
    )
    (net (code "35") (name "Net-(IC2-REG)") (class "Default")
      (node (ref "C32") (pin "1") (pinfunction "1_1") (pintype "passive"))
      (node (ref "IC2") (pin "A2") (pinfunction "REG_A2") (pintype "bidirectional"))
    )
    (net (code "36") (name "Net-(IC3-SDO)") (class "Default")
      (node (ref "IC3") (pin "1") (pinfunction "SDO_1") (pintype "bidirectional"))
      (node (ref "R3") (pin "2") (pinfunction "2_2") (pintype "bidirectional"))
    )
    (net (code "37") (name "Net-(IC9-SCL)") (class "Default")
      (node (ref "IC9") (pin "D1") (pinfunction "SCL_D1") (pintype "bidirectional"))
      (node (ref "R4") (pin "2") (pinfunction "2_2") (pintype "bidirectional"))
    )
    (net (code "38") (name "Net-(IC9-SDA)") (class "Default")
      (node (ref "IC9") (pin "E1") (pinfunction "SDA_E1") (pintype "bidirectional"))
      (node (ref "R2") (pin "2") (pinfunction "2_2") (pintype "bidirectional"))
    )
    (net (code "39") (name "Net-(J4-CC1)") (class "Default")
      (node (ref "J4") (pin "A5") (pinfunction "CC1_A5") (pintype "bidirectional"))
      (node (ref "R1_USB") (pin "2") (pinfunction "2_2") (pintype "bidirectional"))
    )
    (net (code "40") (name "Net-(J4-CC2)") (class "Default")
      (node (ref "J4") (pin "B5") (pinfunction "CC2_B5") (pintype "bidirectional"))
      (node (ref "R2_USB") (pin "1") (pinfunction "1_1") (pintype "bidirectional"))
    )
    (net (code "41") (name "Net-(L2-Pad2)") (class "Default")
      (node (ref "L2") (pin "2") (pinfunction "2_2") (pintype "passive"))
      (node (ref "L3") (pin "1") (pinfunction "1_1") (pintype "passive"))
    )
    (net (code "42") (name "Net-(R1_EP_DR-Pad1)") (class "Default")
      (node (ref "R1_EP_DR") (pin "1") (pinfunction "1_1") (pintype "bidirectional"))
      (node (ref "R_TYPE_SEL") (pin "2") (pinfunction "2_2") (pintype "bidirectional"))
      (node (ref "SJ1") (pin "2") (pinfunction "2_2") (pintype "passive"))
    )
    (net (code "43") (name "Net-(U$1-ANT)") (class "Default")
      (node (ref "C3") (pin "1") (pinfunction "1_1") (pintype "passive"))
      (node (ref "L1") (pin "1") (pinfunction "1_1") (pintype "passive"))
      (node (ref "U$1") (pin "P$H23") (pinfunction "ANT_P$H23") (pintype "bidirectional"))
    )
    (net (code "44") (name "Net-(U$1-DCC)") (class "Default")
      (node (ref "L3") (pin "2") (pinfunction "2_2") (pintype "passive"))
      (node (ref "U$1") (pin "P$B3") (pinfunction "DCC_P$B3") (pintype "output"))
    )
    (net (code "45") (name "Net-(U$1-DEC1)") (class "Default")
      (node (ref "C5") (pin "1") (pinfunction "1_1") (pintype "passive"))
      (node (ref "U$1") (pin "P$C1") (pinfunction "DEC1_P$C1") (pintype "power_in"))
    )
    (net (code "46") (name "Net-(U$1-DEC2)") (class "Default")
      (node (ref "C13") (pin "1") (pinfunction "1_1") (pintype "passive"))
      (node (ref "U$1") (pin "P$A18") (pinfunction "DEC2_P$A18") (pintype "bidirectional"))
    )
    (net (code "47") (name "Net-(U$1-DEC3V3)") (class "Default")
      (node (ref "C20") (pin "1") (pinfunction "1_1") (pintype "passive"))
      (node (ref "U$1") (pin "P$AC5") (pinfunction "DEC3V3_P$AC5") (pintype "bidirectional"))
    )
    (net (code "48") (name "Net-(U$1-DEC5)") (class "Default")
      (node (ref "C9") (pin "1") (pinfunction "1_1") (pintype "passive"))
      (node (ref "U$1") (pin "P$N24") (pinfunction "DEC5_P$N24") (pintype "bidirectional"))
    )
    (net (code "49") (name "Net-(U$1-XC1)") (class "Default")
      (node (ref "C1") (pin "1") (pinfunction "1_1") (pintype "passive"))
      (node (ref "U$1") (pin "P$B24") (pinfunction "XC1_P$B24") (pintype "input"))
      (node (ref "X1") (pin "1") (pinfunction "1_1") (pintype "passive"))
    )
    (net (code "50") (name "Net-(U$1-XC2)") (class "Default")
      (node (ref "C2") (pin "1") (pinfunction "1_1") (pintype "passive"))
      (node (ref "U$1") (pin "P$A23") (pinfunction "XC2_P$A23") (pintype "output"))
      (node (ref "X1") (pin "3") (pinfunction "3_3") (pintype "passive"))
    )
    (net (code "51") (name "OUT+") (class "Default")
      (node (ref "IC2") (pin "A3") (pinfunction "OUT+_A3") (pintype "bidirectional"))
      (node (ref "TP_OP") (pin "TP") (pinfunction "TP_TP") (pintype "input"))
    )
    (net (code "52") (name "OUT-") (class "Default")
      (node (ref "IC2") (pin "C3") (pinfunction "OUT-_C3") (pintype "bidirectional"))
      (node (ref "TP_ON") (pin "TP") (pinfunction "TP_TP") (pintype "input"))
    )
    (net (code "53") (name "P0.04") (class "Default")
      (node (ref "U$1") (pin "P$J1") (pinfunction "P0.04/AIN2_P$J1") (pintype "bidirectional"))
    )
    (net (code "54") (name "P0.09") (class "Default")
      (node (ref "U$1") (pin "P$L24") (pinfunction "P0.09/NFC1_P$L24") (pintype "bidirectional"))
    )
    (net (code "55") (name "P0.13") (class "Default")
      (node (ref "C30") (pin "2") (pinfunction "2_2") (pintype "passive"))
      (node (ref "R12") (pin "1") (pinfunction "1_1") (pintype "bidirectional"))
      (node (ref "SW_UP") (pin "2") (pinfunction "2_2") (pintype "passive"))
      (node (ref "U$1") (pin "P$AD8") (pinfunction "P0.13_P$AD8") (pintype "bidirectional"))
    )
    (net (code "56") (name "P0.14") (class "Default")
      (node (ref "C31") (pin "2") (pinfunction "2_2") (pintype "passive"))
      (node (ref "R11") (pin "1") (pinfunction "1_1") (pintype "bidirectional"))
      (node (ref "SW_ENT") (pin "2") (pinfunction "2_2") (pintype "passive"))
      (node (ref "U$1") (pin "P$AC9") (pinfunction "P0.14_P$AC9") (pintype "bidirectional"))
    )
    (net (code "57") (name "P0.19") (class "Default")
      (node (ref "U$1") (pin "P$AC15") (pinfunction "P0.19_P$AC15") (pintype "bidirectional"))
    )
    (net (code "58") (name "P0.20") (class "Default")
      (node (ref "U$1") (pin "P$AD16") (pinfunction "P0.20_P$AD16") (pintype "bidirectional"))
    )
    (net (code "59") (name "P0.21") (class "Default")
      (node (ref "U$1") (pin "P$AC17") (pinfunction "P0.21_P$AC17") (pintype "bidirectional"))
    )
    (net (code "60") (name "P0.22") (class "Default")
      (node (ref "U$1") (pin "P$AD18") (pinfunction "P0.22_P$AD18") (pintype "bidirectional"))
    )
    (net (code "61") (name "P0.23") (class "Default")
      (node (ref "U$1") (pin "P$AC19") (pinfunction "P0.23_P$AC19") (pintype "bidirectional"))
    )
    (net (code "62") (name "P0.24") (class "Default")
      (node (ref "U$1") (pin "P$AD20") (pinfunction "P0.24_P$AD20") (pintype "bidirectional"))
    )
    (net (code "63") (name "P0.25") (class "Default")
      (node (ref "U$1") (pin "P$AC21") (pinfunction "P0.25_P$AC21") (pintype "bidirectional"))
    )
    (net (code "64") (name "P0.27") (class "Default")
      (node (ref "U$1") (pin "P$G1") (pinfunction "P0.26_P$G1") (pintype "bidirectional"))
      (node (ref "U$1") (pin "P$H2") (pinfunction "P0.27_P$H2") (pintype "bidirectional"))
    )
    (net (code "65") (name "P1.01") (class "Default")
      (node (ref "Q1") (pin "1") (pinfunction "G_1") (pintype "bidirectional"))
      (node (ref "R_PWR_EPD") (pin "1") (pinfunction "1_1") (pintype "bidirectional"))
      (node (ref "U$1") (pin "P$Y23") (pinfunction "P1.01_P$Y23") (pintype "bidirectional"))
    )
    (net (code "66") (name "P1.02") (class "Default")
      (node (ref "C29") (pin "2") (pinfunction "2_2") (pintype "passive"))
      (node (ref "R13") (pin "1") (pinfunction "1_1") (pintype "bidirectional"))
      (node (ref "SW_DN") (pin "2") (pinfunction "2_2") (pintype "passive"))
      (node (ref "U$1") (pin "P$W24") (pinfunction "P1.02_P$W24") (pintype "bidirectional"))
    )
    (net (code "67") (name "P1.03") (class "Default")
      (node (ref "U$1") (pin "P$V23") (pinfunction "P1.03_P$V23") (pintype "bidirectional"))
    )
    (net (code "68") (name "P1.04") (class "Default")
      (node (ref "U$1") (pin "P$U24") (pinfunction "P1.04_P$U24") (pintype "bidirectional"))
    )
    (net (code "69") (name "P1.05") (class "Default")
      (node (ref "U$1") (pin "P$T23") (pinfunction "P1.05_P$T23") (pintype "bidirectional"))
    )
    (net (code "70") (name "P1.06") (class "Default")
      (node (ref "U$1") (pin "P$R24") (pinfunction "P1.06_P$R24") (pintype "bidirectional"))
    )
    (net (code "71") (name "P1.07") (class "Default")
      (node (ref "U$1") (pin "P$P23") (pinfunction "P1.07_P$P23") (pintype "bidirectional"))
    )
    (net (code "72") (name "P1.09") (class "Default")
      (node (ref "U$1") (pin "P$R1") (pinfunction "P1.09_P$R1") (pintype "bidirectional"))
    )
    (net (code "73") (name "PMIC_INT") (class "Default")
      (node (ref "IC1") (pin "A1") (pinfunction "~{INT}_A1") (pintype "bidirectional"))
      (node (ref "U$1") (pin "P$T2") (pinfunction "P0.11_P$T2") (pintype "bidirectional"))
    )
    (net (code "74") (name "PREVGH") (class "Default")
      (node (ref "D5") (pin "1") (pinfunction "K_1") (pintype "bidirectional"))
      (node (ref "EPD_C9") (pin "2") (pinfunction "2_2") (pintype "passive"))
      (node (ref "J1") (pin "21") (pinfunction "21_21") (pintype "bidirectional"))
    )
    (net (code "75") (name "PREVGL") (class "Default")
      (node (ref "D2") (pin "2") (pinfunction "A_2") (pintype "bidirectional"))
      (node (ref "EPD_C11") (pin "2") (pinfunction "2_2") (pintype "passive"))
      (node (ref "J1") (pin "23") (pinfunction "23_23") (pintype "bidirectional"))
    )
    (net (code "76") (name "RESE") (class "Default")
      (node (ref "J1") (pin "3") (pinfunction "3_3") (pintype "bidirectional"))
      (node (ref "Q3") (pin "2") (pinfunction "S_2") (pintype "bidirectional"))
      (node (ref "R1_EP_DR") (pin "2") (pinfunction "2_2") (pintype "bidirectional"))
    )
    (net (code "77") (name "RESET") (class "Default")
      (node (ref "J2") (pin "6") (pinfunction "6_6") (pintype "bidirectional"))
      (node (ref "TP_RESET") (pin "TP") (pinfunction "TP_TP") (pintype "input"))
      (node (ref "U$1") (pin "P$AC13") (pinfunction "P0.18/RESET_P$AC13") (pintype "bidirectional"))
    )
    (net (code "78") (name "SCK") (class "Default")
      (node (ref "J1") (pin "13") (pinfunction "13_13") (pintype "bidirectional"))
    )
    (net (code "79") (name "SCL") (class "Default")
      (node (ref "IC1") (pin "B1") (pinfunction "SCL_B1") (pintype "bidirectional"))
      (node (ref "IC2") (pin "C1") (pinfunction "SCL_C1") (pintype "bidirectional"))
      (node (ref "IC3") (pin "12") (pinfunction "SCX_12") (pintype "bidirectional"))
      (node (ref "R17") (pin "2") (pinfunction "2_2") (pintype "bidirectional"))
      (node (ref "R4") (pin "1") (pinfunction "1_1") (pintype "bidirectional"))
      (node (ref "TP_SCL") (pin "TP") (pinfunction "TP_TP") (pintype "input"))
      (node (ref "U$1") (pin "P$M2") (pinfunction "P0.07_P$M2") (pintype "bidirectional"))
      (node (ref "U3") (pin "7") (pinfunction "SCL_7") (pintype "input"))
    )
    (net (code "80") (name "SDA") (class "Default")
      (node (ref "IC1") (pin "C1") (pinfunction "SDA_C1") (pintype "bidirectional"))
      (node (ref "IC2") (pin "B2") (pinfunction "SDA_B2") (pintype "bidirectional"))
      (node (ref "IC3") (pin "2") (pinfunction "SDX_2") (pintype "bidirectional"))
      (node (ref "R18") (pin "2") (pinfunction "2_2") (pintype "bidirectional"))
      (node (ref "R2") (pin "1") (pinfunction "1_1") (pintype "bidirectional"))
      (node (ref "TP_SDA") (pin "TP") (pinfunction "TP_TP") (pintype "input"))
      (node (ref "U$1") (pin "P$L1") (pinfunction "P0.06_P$L1") (pintype "bidirectional"))
      (node (ref "U3") (pin "8") (pinfunction "SDA_8") (pintype "bidirectional"))
    )
    (net (code "81") (name "SWDCLK") (class "Default")
      (node (ref "J2") (pin "4") (pinfunction "4_4") (pintype "bidirectional"))
      (node (ref "TP_SWDCLK") (pin "TP") (pinfunction "TP_TP") (pintype "input"))
      (node (ref "U$1") (pin "P$AA24") (pinfunction "SWDCLK_P$AA24") (pintype "input"))
    )
    (net (code "82") (name "SWDIO") (class "Default")
      (node (ref "J2") (pin "2") (pinfunction "2_2") (pintype "bidirectional"))
      (node (ref "TP_SWDIO") (pin "TP") (pinfunction "TP_TP") (pintype "input"))
      (node (ref "U$1") (pin "P$AC24") (pinfunction "SWDIO_P$AC24") (pintype "bidirectional"))
    )
    (net (code "83") (name "SWO") (class "Default")
      (node (ref "TP_SWO") (pin "TP") (pinfunction "TP_TP") (pintype "input"))
      (node (ref "U$1") (pin "P$AD22") (pinfunction "P1.00_P$AD22") (pintype "bidirectional"))
    )
    (net (code "84") (name "VBAT") (class "Default")
      (node (ref "C27") (pin "2") (pinfunction "2_2") (pintype "passive"))
      (node (ref "C37") (pin "2") (pinfunction "2_2") (pintype "passive"))
      (node (ref "IC1") (pin "C2") (pinfunction "BAT_C2") (pintype "bidirectional"))
      (node (ref "TP_VBAT") (pin "TP") (pinfunction "TP_TP") (pintype "input"))
      (node (ref "U3") (pin "2") (pinfunction "CELL_2") (pintype "power_in"))
      (node (ref "U3") (pin "3") (pinfunction "VDD_3") (pintype "power_in"))
    )
    (net (code "85") (name "VBUS") (class "Default")
      (node (ref "C21") (pin "1") (pinfunction "1_1") (pintype "passive"))
      (node (ref "C38") (pin "1") (pinfunction "1_1") (pintype "passive"))
      (node (ref "C42") (pin "1") (pinfunction "1_1") (pintype "passive"))
      (node (ref "C43") (pin "1") (pinfunction "1_1") (pintype "passive"))
      (node (ref "D3") (pin "5") (pinfunction "VBUS_5") (pintype "bidirectional"))
      (node (ref "IC1") (pin "A2") (pinfunction "IN_A2") (pintype "bidirectional"))
      (node (ref "J4") (pin "A4_B9") (pinfunction "VBUS_A4_B9") (pintype "power_in"))
      (node (ref "J4") (pin "A9_B4") (pinfunction "VBUS_A9_B4") (pintype "power_in"))
      (node (ref "U$1") (pin "P$AD2") (pinfunction "VBUS_P$AD2") (pintype "power_in"))
    )
    (net (code "86") (name "VREG") (class "Default")
      (node (ref "C23") (pin "2") (pinfunction "2_2") (pintype "passive"))
      (node (ref "C24") (pin "2") (pinfunction "2_2") (pintype "passive"))
      (node (ref "C39") (pin "1") (pinfunction "1_1") (pintype "passive"))
      (node (ref "IC1") (pin "B2") (pinfunction "SYS_B2") (pintype "bidirectional"))
      (node (ref "IC9") (pin "A1") (pinfunction "EN_A1") (pintype "bidirectional"))
      (node (ref "IC9") (pin "A2") (pinfunction "VIN_1_A2") (pintype "bidirectional"))
      (node (ref "IC9") (pin "A3") (pinfunction "VIN_2_A3") (pintype "bidirectional"))
      (node (ref "TP_VREG") (pin "TP") (pinfunction "TP_TP") (pintype "input"))
    )
    (net (code "87") (name "unconnected-(ANT1-NC-Pad2)") (class "Default")
      (node (ref "ANT1") (pin "2") (pinfunction "NC_2") (pintype "no_connect"))
    )
    (net (code "88") (name "unconnected-(IC3-ASCL-Pad11)") (class "Default")
      (node (ref "IC3") (pin "11") (pinfunction "ASCL_11") (pintype "bidirectional"))
    )
    (net (code "89") (name "unconnected-(IC3-ASDA-Pad4)") (class "Default")
      (node (ref "IC3") (pin "4") (pinfunction "ASDA_4") (pintype "bidirectional"))
    )
    (net (code "90") (name "unconnected-(J1-Pad1)") (class "Default")
      (node (ref "J1") (pin "1") (pinfunction "1_1") (pintype "bidirectional"))
    )
    (net (code "91") (name "unconnected-(J1-Pad6)") (class "Default")
      (node (ref "J1") (pin "6") (pinfunction "6_6") (pintype "bidirectional"))
    )
    (net (code "92") (name "unconnected-(J1-Pad7)") (class "Default")
      (node (ref "J1") (pin "7") (pinfunction "7_7") (pintype "bidirectional"))
    )
    (net (code "93") (name "unconnected-(J4-SBU1-PadA8)") (class "Default")
      (node (ref "J4") (pin "A8") (pinfunction "SBU1_A8") (pintype "bidirectional"))
    )
    (net (code "94") (name "unconnected-(J4-SBU2-PadB8)") (class "Default")
      (node (ref "J4") (pin "B8") (pinfunction "SBU2_B8") (pintype "bidirectional"))
    )
    (net (code "95") (name "unconnected-(U$1-DCCH-PadP$AB2)") (class "Default")
      (node (ref "U$1") (pin "P$AB2") (pinfunction "DCCH_P$AB2") (pintype "bidirectional"))
    )
    (net (code "96") (name "unconnected-(U$1-P0.02{slash}AIN0-PadP$A12)") (class "Default")
      (node (ref "U$1") (pin "P$A12") (pinfunction "P0.02/AIN0_P$A12") (pintype "bidirectional"))
    )
    (net (code "97") (name "unconnected-(U$1-P0.03{slash}AIN1-PadP$B13)") (class "Default")
      (node (ref "U$1") (pin "P$B13") (pinfunction "P0.03/AIN1_P$B13") (pintype "bidirectional"))
    )
    (net (code "98") (name "unconnected-(U$1-P0.28{slash}AIN4-PadP$B11)") (class "Default")
      (node (ref "U$1") (pin "P$B11") (pinfunction "P0.28/AIN4_P$B11") (pintype "bidirectional"))
    )
    (net (code "99") (name "unconnected-(U$1-P0.29{slash}AIN5-PadP$A10)") (class "Default")
      (node (ref "U$1") (pin "P$A10") (pinfunction "P0.29/AIN5_P$A10") (pintype "bidirectional"))
    )
    (net (code "100") (name "unconnected-(U$1-P0.30{slash}AIN6-PadP$B9)") (class "Default")
      (node (ref "U$1") (pin "P$B9") (pinfunction "P0.30/AIN6_P$B9") (pintype "bidirectional"))
    )
    (net (code "101") (name "unconnected-(U$1-P0.31{slash}AIN7-PadP$A8)") (class "Default")
      (node (ref "U$1") (pin "P$A8") (pinfunction "P0.31/AIN7_P$A8") (pintype "bidirectional"))
    )
    (net (code "102") (name "unconnected-(U$1-P1.10-PadP$A20)") (class "Default")
      (node (ref "U$1") (pin "P$A20") (pinfunction "P1.10_P$A20") (pintype "bidirectional"))
    )
    (net (code "103") (name "unconnected-(U$1-P1.11-PadP$B19)") (class "Default")
      (node (ref "U$1") (pin "P$B19") (pinfunction "P1.11_P$B19") (pintype "bidirectional"))
    )
    (net (code "104") (name "unconnected-(U$1-P1.12-PadP$B17)") (class "Default")
      (node (ref "U$1") (pin "P$B17") (pinfunction "P1.12_P$B17") (pintype "bidirectional"))
    )
    (net (code "105") (name "unconnected-(U$1-P1.13-PadP$A16)") (class "Default")
      (node (ref "U$1") (pin "P$A16") (pinfunction "P1.13_P$A16") (pintype "bidirectional"))
    )
    (net (code "106") (name "unconnected-(U$1-P1.14-PadP$B15)") (class "Default")
      (node (ref "U$1") (pin "P$B15") (pinfunction "P1.14_P$B15") (pintype "bidirectional"))
    )
    (net (code "107") (name "unconnected-(U$1-P1.15-PadP$A14)") (class "Default")
      (node (ref "U$1") (pin "P$A14") (pinfunction "P1.15_P$A14") (pintype "bidirectional"))
    )
  )
)
